# SEMLIC_V2.net
KiCad netlist of a schematic drawn in EAGLE
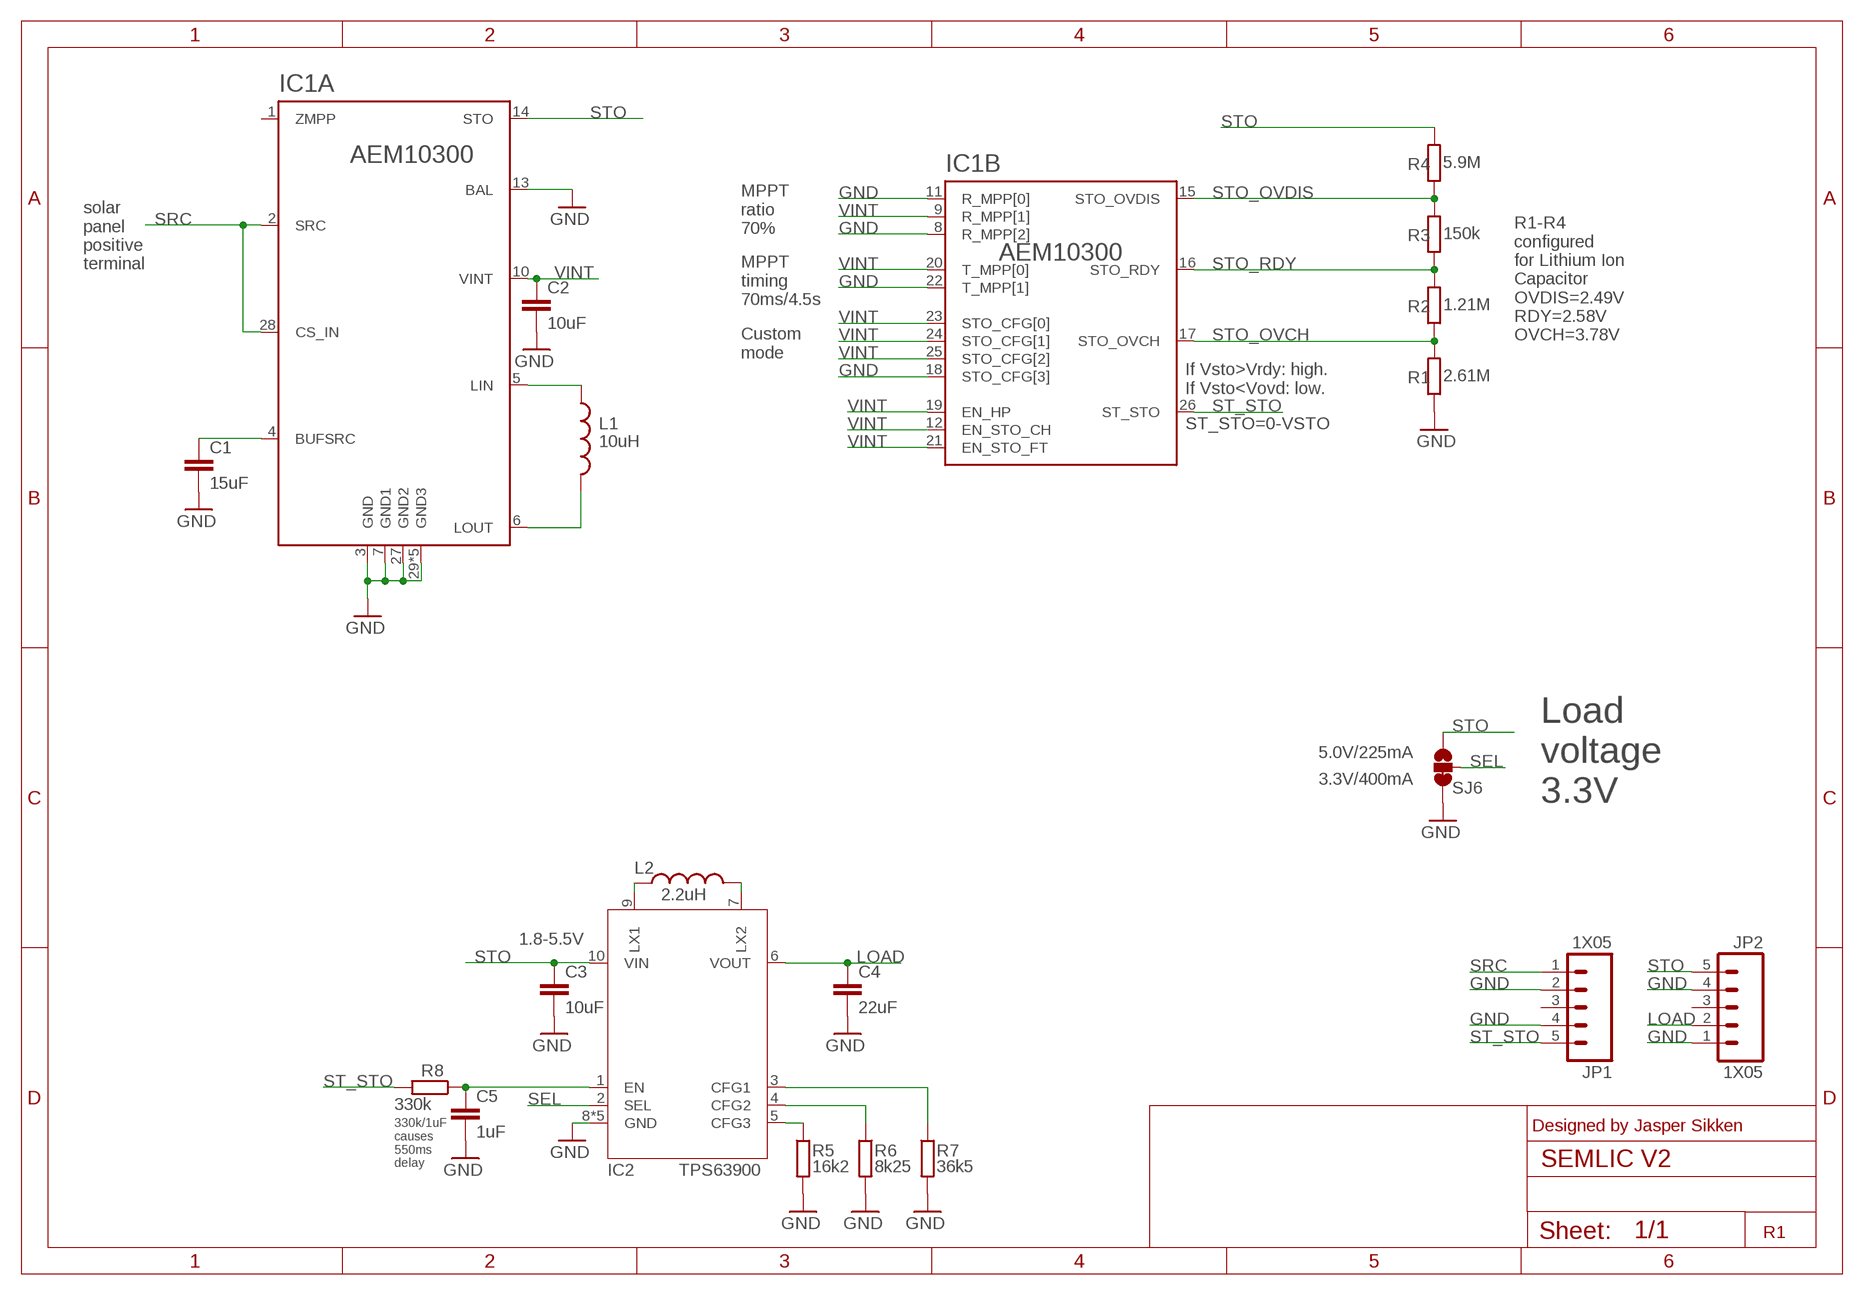
[diagram p0: schematic, sheet 1]

(export (version "E")
  (design (tool "Eeschema 10.0.6"))
  (components
    (comp (ref "C1")
      (value "15uF")
      (footprint "eagle-import:C0402")
      (libsource (lib "eagle-import") (part "C_0402"))
    )
    (comp (ref "C2")
      (value "10uF")
      (footprint "eagle-import:C0402")
      (libsource (lib "eagle-import") (part "C_0402"))
    )
    (comp (ref "C3")
      (value "10uF")
      (footprint "eagle-import:C0603")
      (fields (field (name "MF") "Taiyo Yuden") (field (name "MPN") "LMK107BBJ106MALT"))
      (libsource (lib "eagle-import") (part "C0603_10UF"))
    )
    (comp (ref "C4")
      (value "22uF")
      (footprint "eagle-import:C0603")
      (fields (field (name "MF") "Murata") (field (name "MPN") "GRM188R61A226ME15D"))
      (libsource (lib "eagle-import") (part "C0603_22UF"))
    )
    (comp (ref "C5")
      (value "1uF")
      (footprint "eagle-import:C0402")
      (libsource (lib "eagle-import") (part "C_0402"))
    )
    (comp (ref "IC1")
      (value "AEM10300")
      (footprint "eagle-import:QFN28P4X4")
      (libsource (lib "eagle-import") (part "AEM10300"))
    )
    (comp (ref "IC2")
      (value "TPS63900")
      (footprint "eagle-import:WSON10")
      (libsource (lib "eagle-import") (part "TPS63900"))
    )
    (comp (ref "JP1")
      (value "1X05")
      (footprint "eagle-import:1X05_2.54MM_ROUND_NOSILK")
      (libsource (lib "eagle-import") (part "1X05"))
    )
    (comp (ref "JP2")
      (value "1X05")
      (footprint "eagle-import:1X05_2.54MM_ROUND_NOSILK")
      (libsource (lib "eagle-import") (part "1X05"))
    )
    (comp (ref "L1")
      (value "10uH")
      (footprint "eagle-import:L_1008_[2520]")
      (fields (field (name "MF") "MURATA") (field (name "MPN") "DFE252010F-100"))
      (libsource (lib "eagle-import") (part "L"))
    )
    (comp (ref "L2")
      (value "2.2uH")
      (footprint "eagle-import:L_1008_[2520]")
      (fields (field (name "MF") "Murata") (field (name "MPN") "DFE252012F-2R2M=P2"))
      (libsource (lib "eagle-import") (part "L2"))
    )
    (comp (ref "R1")
      (value "2.61M")
      (footprint "eagle-import:R0402")
      (fields (field (name "MF") "Walsin") (field (name "MPN") "WR04X1004FTL"))
      (libsource (lib "eagle-import") (part "R0402_1M"))
    )
    (comp (ref "R2")
      (value "1.21M")
      (footprint "eagle-import:R0402")
      (fields (field (name "MF") "Walsin") (field (name "MPN") "WR04X1004FTL"))
      (libsource (lib "eagle-import") (part "R0402_1M"))
    )
    (comp (ref "R3")
      (value "150k")
      (footprint "eagle-import:R0402")
      (fields (field (name "MF") "Walsin") (field (name "MPN") "WR04X1004FTL"))
      (libsource (lib "eagle-import") (part "R0402_1M"))
    )
    (comp (ref "R4")
      (value "5.9M")
      (footprint "eagle-import:R0402")
      (fields (field (name "MF") "Walsin") (field (name "MPN") "WR04X1004FTL"))
      (libsource (lib "eagle-import") (part "R0402_1M"))
    )
    (comp (ref "R5")
      (value "16k2")
      (footprint "eagle-import:R0402")
      (fields (field (name "MF") "Walsin") (field (name "MPN") "WR04X1004FTL"))
      (libsource (lib "eagle-import") (part "R0402_1M"))
    )
    (comp (ref "R6")
      (value "8k25")
      (footprint "eagle-import:R0402")
      (fields (field (name "MF") "Walsin") (field (name "MPN") "WR04X1004FTL"))
      (libsource (lib "eagle-import") (part "R0402_1M"))
    )
    (comp (ref "R7")
      (value "36k5")
      (footprint "eagle-import:R0402")
      (fields (field (name "MF") "Walsin") (field (name "MPN") "WR04X1004FTL"))
      (libsource (lib "eagle-import") (part "R0402_1M"))
    )
    (comp (ref "R8")
      (value "330k")
      (footprint "eagle-import:R0402")
      (fields (field (name "MF") "Walsin") (field (name "MPN") "WR04X1004FTL"))
      (libsource (lib "eagle-import") (part "R0402_1M"))
    )
    (comp (ref "SJ6")
      (value "SOLDERJUMPER_3WAY_12SHORT3WAY")
      (footprint "eagle-import:SJ_3S_NC_0402")
      (libsource (lib "eagle-import") (part "SOLDERJUMPER_3WAY_12SHORT3WAY"))
    )
  )
  (nets
    (net (code "1") (name "/LOAD") (class "Default")
      (node (ref "C4") (pin "1") (pinfunction "1_1") (pintype "passive"))
      (node (ref "IC2") (pin "6") (pinfunction "VOUT_6") (pintype "bidirectional"))
      (node (ref "JP2") (pin "2") (pinfunction "2_2") (pintype "passive"))
    )
    (net (code "2") (name "/SEL") (class "Default")
      (node (ref "IC2") (pin "2") (pinfunction "SEL_2") (pintype "bidirectional"))
      (node (ref "SJ6") (pin "2") (pinfunction "2_2") (pintype "bidirectional"))
    )
    (net (code "3") (name "/SRC") (class "Default")
      (node (ref "IC1") (pin "2") (pinfunction "SRC_2") (pintype "bidirectional"))
      (node (ref "IC1") (pin "28") (pinfunction "CS_IN_28") (pintype "bidirectional"))
      (node (ref "JP1") (pin "1") (pinfunction "1_1") (pintype "passive"))
    )
    (net (code "4") (name "/STO") (class "Default")
      (node (ref "C3") (pin "1") (pinfunction "1_1") (pintype "passive"))
      (node (ref "IC1") (pin "14") (pinfunction "STO_14") (pintype "bidirectional"))
      (node (ref "IC2") (pin "10") (pinfunction "VIN_10") (pintype "bidirectional"))
      (node (ref "JP2") (pin "5") (pinfunction "5_5") (pintype "passive"))
      (node (ref "R4") (pin "2") (pinfunction "2_2") (pintype "passive"))
      (node (ref "SJ6") (pin "3") (pinfunction "3_3") (pintype "bidirectional"))
    )
    (net (code "5") (name "/STO_OVCH") (class "Default")
      (node (ref "IC1") (pin "17") (pinfunction "STO_OVCH_17") (pintype "bidirectional"))
      (node (ref "R1") (pin "2") (pinfunction "2_2") (pintype "passive"))
      (node (ref "R2") (pin "1") (pinfunction "1_1") (pintype "passive"))
    )
    (net (code "6") (name "/STO_OVDIS") (class "Default")
      (node (ref "IC1") (pin "15") (pinfunction "STO_OVDIS_15") (pintype "bidirectional"))
      (node (ref "R3") (pin "2") (pinfunction "2_2") (pintype "passive"))
      (node (ref "R4") (pin "1") (pinfunction "1_1") (pintype "passive"))
    )
    (net (code "7") (name "/STO_RDY") (class "Default")
      (node (ref "IC1") (pin "16") (pinfunction "STO_RDY_16") (pintype "bidirectional"))
      (node (ref "R2") (pin "2") (pinfunction "2_2") (pintype "passive"))
      (node (ref "R3") (pin "1") (pinfunction "1_1") (pintype "passive"))
    )
    (net (code "8") (name "/ST_STO") (class "Default")
      (node (ref "IC1") (pin "26") (pinfunction "ST_STO_26") (pintype "bidirectional"))
      (node (ref "JP1") (pin "5") (pinfunction "5_5") (pintype "passive"))
      (node (ref "R8") (pin "2") (pinfunction "2_2") (pintype "passive"))
    )
    (net (code "9") (name "/VINT") (class "Default")
      (node (ref "C2") (pin "1") (pinfunction "1_1") (pintype "passive"))
      (node (ref "IC1") (pin "10") (pinfunction "VINT_10") (pintype "bidirectional"))
      (node (ref "IC1") (pin "12") (pinfunction "EN_STO_CH_12") (pintype "bidirectional"))
      (node (ref "IC1") (pin "19") (pinfunction "EN_HP_19") (pintype "bidirectional"))
      (node (ref "IC1") (pin "20") (pinfunction "T_MPP[0]_20") (pintype "bidirectional"))
      (node (ref "IC1") (pin "21") (pinfunction "EN_STO_FT_21") (pintype "bidirectional"))
      (node (ref "IC1") (pin "23") (pinfunction "STO_CFG[0]_23") (pintype "bidirectional"))
      (node (ref "IC1") (pin "24") (pinfunction "STO_CFG[1]_24") (pintype "bidirectional"))
      (node (ref "IC1") (pin "25") (pinfunction "STO_CFG[2]_25") (pintype "bidirectional"))
      (node (ref "IC1") (pin "9") (pinfunction "R_MPP[1]_9") (pintype "bidirectional"))
    )
    (net (code "10") (name "GND") (class "Default")
      (node (ref "C1") (pin "2") (pinfunction "2_2") (pintype "passive"))
      (node (ref "C2") (pin "2") (pinfunction "2_2") (pintype "passive"))
      (node (ref "C3") (pin "2") (pinfunction "2_2") (pintype "passive"))
      (node (ref "C4") (pin "2") (pinfunction "2_2") (pintype "passive"))
      (node (ref "C5") (pin "2") (pinfunction "2_2") (pintype "passive"))
      (node (ref "IC1") (pin "11") (pinfunction "R_MPP[0]_11") (pintype "bidirectional"))
      (node (ref "IC1") (pin "13") (pinfunction "BAL_13") (pintype "bidirectional"))
      (node (ref "IC1") (pin "18") (pinfunction "STO_CFG[3]_18") (pintype "bidirectional"))
      (node (ref "IC1") (pin "22") (pinfunction "T_MPP[1]_22") (pintype "bidirectional"))
      (node (ref "IC1") (pin "27") (pinfunction "GND2_27") (pintype "bidirectional"))
      (node (ref "IC1") (pin "29") (pinfunction "GND3_29") (pintype "bidirectional"))
      (node (ref "IC1") (pin "3") (pinfunction "GND_3") (pintype "bidirectional"))
      (node (ref "IC1") (pin "7") (pinfunction "GND1_7") (pintype "bidirectional"))
      (node (ref "IC1") (pin "8") (pinfunction "R_MPP[2]_8") (pintype "bidirectional"))
      (node (ref "IC1") (pin "P$1") (pinfunction "GND3_P$1") (pintype "bidirectional"))
      (node (ref "IC1") (pin "P$2") (pinfunction "GND3_P$2") (pintype "bidirectional"))
      (node (ref "IC1") (pin "P$3") (pinfunction "GND3_P$3") (pintype "bidirectional"))
      (node (ref "IC1") (pin "P$4") (pinfunction "GND3_P$4") (pintype "bidirectional"))
      (node (ref "IC2") (pin "29") (pinfunction "GND_29") (pintype "bidirectional"))
      (node (ref "IC2") (pin "8") (pinfunction "GND_8") (pintype "bidirectional"))
      (node (ref "IC2") (pin "P$2") (pinfunction "GND_P$2") (pintype "bidirectional"))
      (node (ref "IC2") (pin "P$4") (pinfunction "GND_P$4") (pintype "bidirectional"))
      (node (ref "IC2") (pin "P$5") (pinfunction "GND_P$5") (pintype "bidirectional"))
      (node (ref "JP1") (pin "2") (pinfunction "2_2") (pintype "passive"))
      (node (ref "JP1") (pin "4") (pinfunction "4_4") (pintype "passive"))
      (node (ref "JP2") (pin "1") (pinfunction "1_1") (pintype "passive"))
      (node (ref "JP2") (pin "4") (pinfunction "4_4") (pintype "passive"))
      (node (ref "R1") (pin "1") (pinfunction "1_1") (pintype "passive"))
      (node (ref "R5") (pin "2") (pinfunction "2_2") (pintype "passive"))
      (node (ref "R6") (pin "2") (pinfunction "2_2") (pintype "passive"))
      (node (ref "R7") (pin "2") (pinfunction "2_2") (pintype "passive"))
      (node (ref "SJ6") (pin "1") (pinfunction "1_1") (pintype "bidirectional"))
    )
    (net (code "11") (name "Net-(IC1A-BUFSRC)") (class "Default")
      (node (ref "C1") (pin "1") (pinfunction "1_1") (pintype "passive"))
      (node (ref "IC1") (pin "4") (pinfunction "BUFSRC_4") (pintype "bidirectional"))
    )
    (net (code "12") (name "Net-(IC1A-LIN)") (class "Default")
      (node (ref "IC1") (pin "5") (pinfunction "LIN_5") (pintype "bidirectional"))
      (node (ref "L1") (pin "1") (pinfunction "1_1") (pintype "passive"))
    )
    (net (code "13") (name "Net-(IC1A-LOUT)") (class "Default")
      (node (ref "IC1") (pin "6") (pinfunction "LOUT_6") (pintype "bidirectional"))
      (node (ref "L1") (pin "2") (pinfunction "2_2") (pintype "passive"))
    )
    (net (code "14") (name "Net-(IC2-CFG1)") (class "Default")
      (node (ref "IC2") (pin "3") (pinfunction "CFG1_3") (pintype "bidirectional"))
      (node (ref "R7") (pin "1") (pinfunction "1_1") (pintype "passive"))
    )
    (net (code "15") (name "Net-(IC2-CFG2)") (class "Default")
      (node (ref "IC2") (pin "4") (pinfunction "CFG2_4") (pintype "bidirectional"))
      (node (ref "R6") (pin "1") (pinfunction "1_1") (pintype "passive"))
    )
    (net (code "16") (name "Net-(IC2-CFG3)") (class "Default")
      (node (ref "IC2") (pin "5") (pinfunction "CFG3_5") (pintype "bidirectional"))
      (node (ref "R5") (pin "1") (pinfunction "1_1") (pintype "passive"))
    )
    (net (code "17") (name "Net-(IC2-EN)") (class "Default")
      (node (ref "C5") (pin "1") (pinfunction "1_1") (pintype "passive"))
      (node (ref "IC2") (pin "1") (pinfunction "EN_1") (pintype "bidirectional"))
      (node (ref "R8") (pin "1") (pinfunction "1_1") (pintype "passive"))
    )
    (net (code "18") (name "Net-(IC2-LX1)") (class "Default")
      (node (ref "IC2") (pin "9") (pinfunction "LX1_9") (pintype "bidirectional"))
      (node (ref "L2") (pin "1") (pinfunction "1_1") (pintype "passive"))
    )
    (net (code "19") (name "Net-(IC2-LX2)") (class "Default")
      (node (ref "IC2") (pin "7") (pinfunction "LX2_7") (pintype "bidirectional"))
      (node (ref "L2") (pin "2") (pinfunction "2_2") (pintype "passive"))
    )
    (net (code "20") (name "unconnected-(IC1A-ZMPP-Pad1)") (class "Default")
      (node (ref "IC1") (pin "1") (pinfunction "ZMPP_1") (pintype "bidirectional"))
    )
    (net (code "21") (name "unconnected-(JP1-Pad3)") (class "Default")
      (node (ref "JP1") (pin "3") (pinfunction "3_3") (pintype "passive"))
    )
    (net (code "22") (name "unconnected-(JP2-Pad3)") (class "Default")
      (node (ref "JP2") (pin "3") (pinfunction "3_3") (pintype "passive"))
    )
  )
)
